# SCH_Batteries-Recharger_2025-04-03.net
KiCad netlist of a schematic drawn in EasyEDA
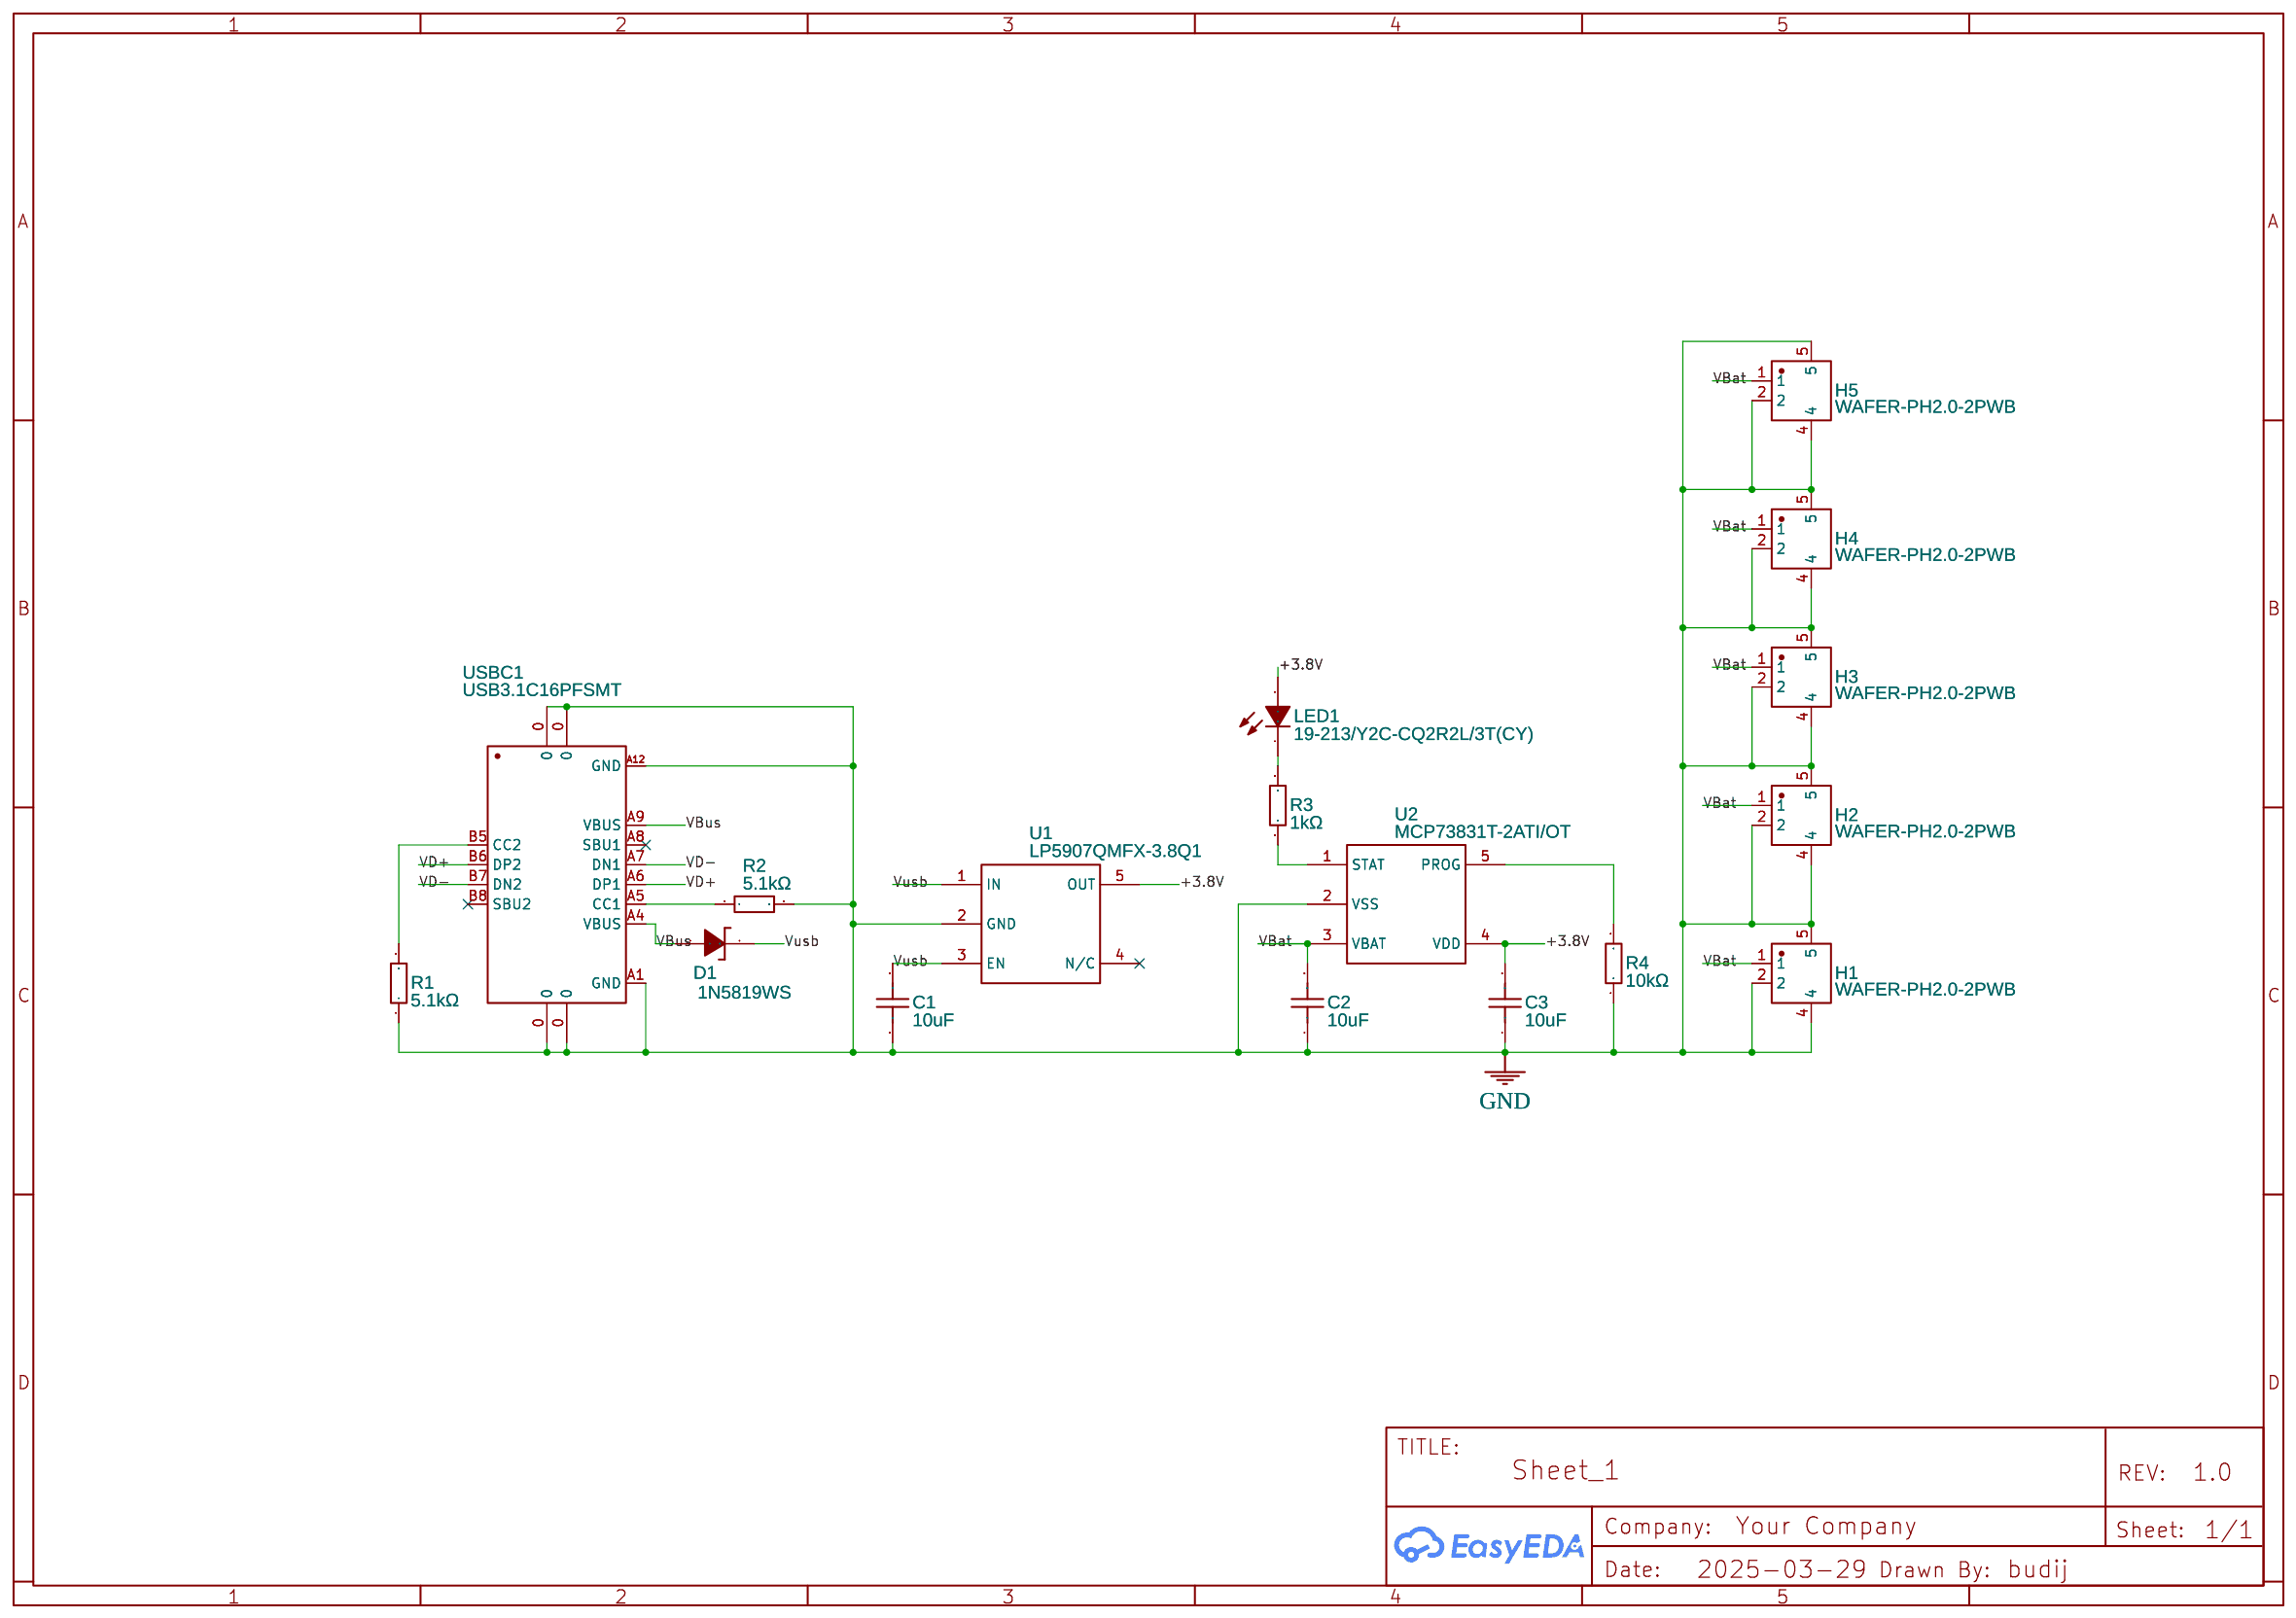
[diagram p0: schematic sheet]

(export (version "E")
  (design (tool "Eeschema 10.0.6"))
  (components
    (comp (ref "C1")
      (value "10uF")
      (fields
        (field (name "Manufacturer Part") "CL10A106KP8NNNC")
        (field (name "Manufacturer") "SAMSUNG(三星)")
      )
      (libsource (lib "") (part "CL10A106KP8NNNC"))
    )
    (comp (ref "C2")
      (value "10uF")
      (fields
        (field (name "Manufacturer Part") "CL10A106KP8NNNC")
        (field (name "Manufacturer") "SAMSUNG(三星)")
      )
      (libsource (lib "") (part "CL10A106KP8NNNC"))
    )
    (comp (ref "C3")
      (value "10uF")
      (fields
        (field (name "Manufacturer Part") "CL10A106KP8NNNC")
        (field (name "Manufacturer") "SAMSUNG(三星)")
      )
      (libsource (lib "") (part "CL10A106KP8NNNC"))
    )
    (comp (ref "D1")
      (value "1N5819WS")
      (fields (field (name "Manufacturer") "Hottech(合科泰)"))
      (libsource (lib "") (part "1N5819WS"))
    )
    (comp (ref "H1")
      (value "WAFER-PH2.0-2PWB")
      (fields (field (name "Manufacturer") "XUNPU(讯普)"))
      (libsource (lib "") (part "WAFER-PH2.0-2PWB"))
    )
    (comp (ref "H2")
      (value "WAFER-PH2.0-2PWB")
      (fields (field (name "Manufacturer") "XUNPU(讯普)"))
      (libsource (lib "") (part "WAFER-PH2.0-2PWB"))
    )
    (comp (ref "H3")
      (value "WAFER-PH2.0-2PWB")
      (fields (field (name "Manufacturer") "XUNPU(讯普)"))
      (libsource (lib "") (part "WAFER-PH2.0-2PWB"))
    )
    (comp (ref "H4")
      (value "WAFER-PH2.0-2PWB")
      (fields (field (name "Manufacturer") "XUNPU(讯普)"))
      (libsource (lib "") (part "WAFER-PH2.0-2PWB"))
    )
    (comp (ref "H5")
      (value "WAFER-PH2.0-2PWB")
      (fields (field (name "Manufacturer") "XUNPU(讯普)"))
      (libsource (lib "") (part "WAFER-PH2.0-2PWB"))
    )
    (comp (ref "LED1")
      (value "19-213/Y2C-CQ2R2L/3T(CY)")
      (fields (field (name "Manufacturer") "EVERLIGHT(亿光)"))
      (libsource (lib "") (part "19-213/Y2C-CQ2R2L/3T(CY)"))
    )
    (comp (ref "R1")
      (value "5.1kΩ")
      (fields
        (field (name "Manufacturer Part") "0603WAF5101T5E")
        (field (name "Manufacturer") "UNI-ROYAL(厚声)")
      )
      (libsource (lib "") (part "0603WAF5101T5E_1"))
    )
    (comp (ref "R2")
      (value "5.1kΩ")
      (fields
        (field (name "Manufacturer Part") "0603WAF5101T5E")
        (field (name "Manufacturer") "UNI-ROYAL(厚声)")
      )
      (libsource (lib "") (part "0603WAF5101T5E"))
    )
    (comp (ref "R3")
      (value "1kΩ")
      (fields
        (field (name "Manufacturer Part") "0603WAF1001T5E")
        (field (name "Manufacturer") "UNI-ROYAL(厚声)")
      )
      (libsource (lib "") (part "0603WAF1001T5E"))
    )
    (comp (ref "R4")
      (value "10kΩ")
      (fields
        (field (name "Manufacturer Part") "0603WAF1002T5E")
        (field (name "Manufacturer") "UNI-ROYAL(厚声)")
      )
      (libsource (lib "") (part "0603WAF1002T5E"))
    )
    (comp (ref "U1")
      (value "LP5907QMFX-3.8Q1")
      (fields (field (name "Manufacturer") "TI(德州仪器)"))
      (libsource (lib "") (part "LP5907QMFX-3.8Q1"))
    )
    (comp (ref "U2")
      (value "MCP73831T-2ATI/OT")
      (fields (field (name "Manufacturer") "MICROCHIP"))
      (libsource (lib "") (part "MCP73831T-2ATI/OT"))
    )
    (comp (ref "USBC1")
      (value "USB3.1C16PFSMT")
      (fields (field (name "Manufacturer") "LCSC"))
      (libsource (lib "") (part "USB3.1C16PFSMT"))
    )
  )
  (nets
    (net (code "1") (name "/+3.8V") (class "Default")
      (node (ref "C3") (pin "2") (pinfunction "2_2") (pintype "unspecified"))
      (node (ref "LED1") (pin "2") (pinfunction "A_2") (pintype "input"))
      (node (ref "U1") (pin "5") (pinfunction "OUT_5") (pintype "unspecified"))
      (node (ref "U2") (pin "4") (pinfunction "VDD_4") (pintype "unspecified"))
    )
    (net (code "2") (name "/VBat") (class "Default")
      (node (ref "C2") (pin "2") (pinfunction "2_2") (pintype "unspecified"))
      (node (ref "H1") (pin "1") (pinfunction "1_1") (pintype "unspecified"))
      (node (ref "H2") (pin "1") (pinfunction "1_1") (pintype "unspecified"))
      (node (ref "H3") (pin "1") (pinfunction "1_1") (pintype "unspecified"))
      (node (ref "H4") (pin "1") (pinfunction "1_1") (pintype "unspecified"))
      (node (ref "H5") (pin "1") (pinfunction "1_1") (pintype "unspecified"))
      (node (ref "U2") (pin "3") (pinfunction "VBAT_3") (pintype "unspecified"))
    )
    (net (code "3") (name "/VBus") (class "Default")
      (node (ref "D1") (pin "2") (pinfunction "A_2") (pintype "unspecified"))
      (node (ref "USBC1") (pin "A4") (pinfunction "VBUS_A4") (pintype "unspecified"))
      (node (ref "USBC1") (pin "A9") (pinfunction "VBUS_A9") (pintype "unspecified"))
    )
    (net (code "4") (name "/VD+") (class "Default")
      (node (ref "USBC1") (pin "A6") (pinfunction "DP1_A6") (pintype "unspecified"))
      (node (ref "USBC1") (pin "B6") (pinfunction "DP2_B6") (pintype "unspecified"))
    )
    (net (code "5") (name "/VD-") (class "Default")
      (node (ref "USBC1") (pin "A7") (pinfunction "DN1_A7") (pintype "unspecified"))
      (node (ref "USBC1") (pin "B7") (pinfunction "DN2_B7") (pintype "unspecified"))
    )
    (net (code "6") (name "/Vusb") (class "Default")
      (node (ref "C1") (pin "2") (pinfunction "2_2") (pintype "unspecified"))
      (node (ref "D1") (pin "1") (pinfunction "C_1") (pintype "unspecified"))
      (node (ref "U1") (pin "1") (pinfunction "IN_1") (pintype "unspecified"))
      (node (ref "U1") (pin "3") (pinfunction "EN_3") (pintype "unspecified"))
    )
    (net (code "7") (name "GND") (class "Default")
      (node (ref "C1") (pin "1") (pinfunction "1_1") (pintype "unspecified"))
      (node (ref "C2") (pin "1") (pinfunction "1_1") (pintype "unspecified"))
      (node (ref "C3") (pin "1") (pinfunction "1_1") (pintype "unspecified"))
      (node (ref "H1") (pin "2") (pinfunction "2_2") (pintype "unspecified"))
      (node (ref "H1") (pin "4") (pinfunction "4_4") (pintype "unspecified"))
      (node (ref "H1") (pin "5") (pinfunction "5_5") (pintype "unspecified"))
      (node (ref "H2") (pin "2") (pinfunction "2_2") (pintype "unspecified"))
      (node (ref "H2") (pin "4") (pinfunction "4_4") (pintype "unspecified"))
      (node (ref "H2") (pin "5") (pinfunction "5_5") (pintype "unspecified"))
      (node (ref "H3") (pin "2") (pinfunction "2_2") (pintype "unspecified"))
      (node (ref "H3") (pin "4") (pinfunction "4_4") (pintype "unspecified"))
      (node (ref "H3") (pin "5") (pinfunction "5_5") (pintype "unspecified"))
      (node (ref "H4") (pin "2") (pinfunction "2_2") (pintype "unspecified"))
      (node (ref "H4") (pin "4") (pinfunction "4_4") (pintype "unspecified"))
      (node (ref "H4") (pin "5") (pinfunction "5_5") (pintype "unspecified"))
      (node (ref "H5") (pin "2") (pinfunction "2_2") (pintype "unspecified"))
      (node (ref "H5") (pin "4") (pinfunction "4_4") (pintype "unspecified"))
      (node (ref "H5") (pin "5") (pinfunction "5_5") (pintype "unspecified"))
      (node (ref "R1") (pin "1") (pinfunction "1_1") (pintype "input"))
      (node (ref "R2") (pin "2") (pinfunction "2_2") (pintype "input"))
      (node (ref "R4") (pin "1") (pinfunction "1_1") (pintype "input"))
      (node (ref "U1") (pin "2") (pinfunction "GND_2") (pintype "unspecified"))
      (node (ref "U2") (pin "2") (pinfunction "VSS_2") (pintype "unspecified"))
      (node (ref "USBC1") (pin "0") (pinfunction "0_0") (pintype "unspecified"))
      (node (ref "USBC1") (pin "A1") (pinfunction "GND_A1") (pintype "unspecified"))
      (node (ref "USBC1") (pin "A12") (pinfunction "GND_A12") (pintype "unspecified"))
    )
    (net (code "8") (name "Net-(LED1-C)") (class "Default")
      (node (ref "LED1") (pin "1") (pinfunction "C_1") (pintype "input"))
      (node (ref "R3") (pin "2") (pinfunction "2_2") (pintype "input"))
    )
    (net (code "9") (name "Net-(U2-PROG)") (class "Default")
      (node (ref "R4") (pin "2") (pinfunction "2_2") (pintype "input"))
      (node (ref "U2") (pin "5") (pinfunction "PROG_5") (pintype "unspecified"))
    )
    (net (code "10") (name "Net-(U2-STAT)") (class "Default")
      (node (ref "R3") (pin "1") (pinfunction "1_1") (pintype "input"))
      (node (ref "U2") (pin "1") (pinfunction "STAT_1") (pintype "unspecified"))
    )
    (net (code "11") (name "Net-(USBC1-CC1)") (class "Default")
      (node (ref "R2") (pin "1") (pinfunction "1_1") (pintype "input"))
      (node (ref "USBC1") (pin "A5") (pinfunction "CC1_A5") (pintype "unspecified"))
    )
    (net (code "12") (name "Net-(USBC1-CC2)") (class "Default")
      (node (ref "R1") (pin "2") (pinfunction "2_2") (pintype "input"))
      (node (ref "USBC1") (pin "B5") (pinfunction "CC2_B5") (pintype "unspecified"))
    )
    (net (code "13") (name "unconnected-(U1-N{slash}C-Pad4)") (class "Default")
      (node (ref "U1") (pin "4") (pinfunction "N/C_4") (pintype "unspecified+no_connect"))
    )
    (net (code "14") (name "unconnected-(USBC1-SBU1-PadA8)") (class "Default")
      (node (ref "USBC1") (pin "A8") (pinfunction "SBU1_A8") (pintype "unspecified+no_connect"))
    )
    (net (code "15") (name "unconnected-(USBC1-SBU2-PadB8)") (class "Default")
      (node (ref "USBC1") (pin "B8") (pinfunction "SBU2_B8") (pintype "unspecified+no_connect"))
    )
  )
)
